# 01-MCU-V2_2.net
KiCad netlist of a schematic drawn in Altium Designer
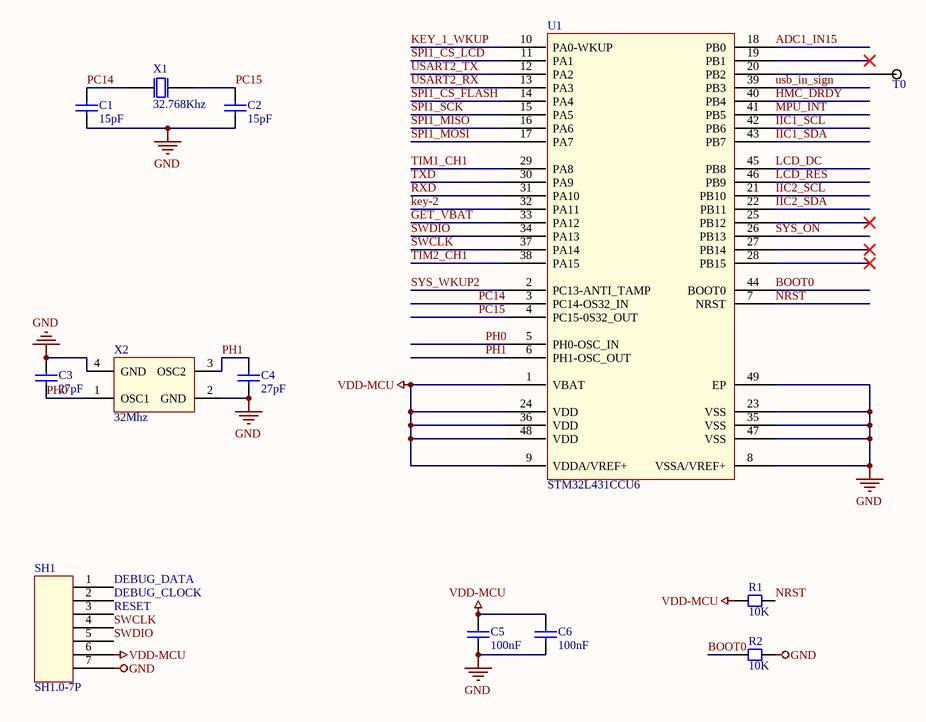
[diagram p0: 01-MCU-V2.2.SchDoc]

(export (version "E")
  (design (tool "Eeschema 10.0.6"))
  (components
    (comp (ref "C1")
      (value "15pF")
      (footprint "CC1005-0402")
      (description "贴片电容")
      (libsource (lib "tianxiaohua_Schlib") (part "Chip capacitor"))
    )
    (comp (ref "C2")
      (value "15pF")
      (footprint "CC1005-0402")
      (description "贴片电容")
      (libsource (lib "tianxiaohua_Schlib") (part "Chip capacitor"))
    )
    (comp (ref "C3")
      (value "27pF")
      (footprint "CC1005-0402")
      (description "贴片电容")
      (libsource (lib "tianxiaohua_Schlib") (part "Chip capacitor"))
    )
    (comp (ref "C4")
      (value "27pF")
      (footprint "CC1005-0402")
      (description "贴片电容")
      (libsource (lib "tianxiaohua_Schlib") (part "Chip capacitor"))
    )
    (comp (ref "C5")
      (value "100nF")
      (footprint "CC1005-0402")
      (description "贴片电容")
      (libsource (lib "tianxiaohua_Schlib") (part "Chip capacitor"))
    )
    (comp (ref "C6")
      (value "100nF")
      (footprint "CC1005-0402")
      (description "贴片电容")
      (libsource (lib "tianxiaohua_Schlib") (part "Chip capacitor"))
    )
    (comp (ref "R1")
      (value "10K")
      (footprint "CR1005-0402")
      (description "贴片电阻")
      (libsource (lib "tianxiaohua_Schlib") (part "Chip resistor"))
    )
    (comp (ref "R2")
      (value "10K")
      (footprint "CR1005-0402")
      (description "贴片电阻")
      (libsource (lib "tianxiaohua_Schlib") (part "Chip resistor"))
    )
    (comp (ref "SH1")
      (value "SH1.0-7P")
      (footprint "SH1.0-7P")
      (description "间距为1mm的端子")
      (libsource (lib "tianxiaohua_Schlib") (part "SH1.0-7P"))
    )
    (comp (ref "T0") (value "测试点") (footprint "测试点") (libsource (lib "tianxiaohua_Schlib") (part "测试点")))
    (comp (ref "U1")
      (value "STM32L431CCU6")
      (footprint "STM32-UFQFPN48_N")
      (description "stm32低功耗单片机 主频80MHz")
      (libsource (lib "tianxiaohua_Schlib") (part "STM32L431CCU6"))
    )
    (comp (ref "X1")
      (value "32.768Khz")
      (footprint "XTAL-2012")
      (description "2012封装的时钟晶振")
      (libsource (lib "tianxiaohua_Schlib") (part "XTAL 2012"))
    )
    (comp (ref "X2")
      (value "32Mhz")
      (footprint "XTAL-2016")
      (description "2016封装的晶振")
      (libsource (lib "tianxiaohua_Schlib") (part "XTAL 2016"))
    )
  )
  (nets
    (net (code "1") (name "/ADC1_IN15") (class "Default")
      (node (ref "U1") (pin "18") (pinfunction "PB0_18") (pintype "passive"))
    )
    (net (code "2") (name "/BOOT0") (class "Default")
      (node (ref "R2") (pin "2") (pinfunction "2_2") (pintype "passive"))
      (node (ref "U1") (pin "44") (pinfunction "BOOT0_44") (pintype "passive"))
    )
    (net (code "3") (name "/DEBUG_CLOCK") (class "Default")
      (node (ref "SH1") (pin "2") (pinfunction "2_2") (pintype "passive"))
    )
    (net (code "4") (name "/DEBUG_DATA") (class "Default") (node (ref "SH1") (pin "1") (pintype "passive")))
    (net (code "5") (name "/GET_VBAT") (class "Default")
      (node (ref "U1") (pin "33") (pinfunction "PA12_33") (pintype "passive"))
    )
    (net (code "6") (name "/HMC_DRDY") (class "Default")
      (node (ref "U1") (pin "40") (pinfunction "PB4_40") (pintype "passive"))
    )
    (net (code "7") (name "/IIC1_SCL") (class "Default")
      (node (ref "U1") (pin "42") (pinfunction "PB6_42") (pintype "passive"))
    )
    (net (code "8") (name "/IIC1_SDA") (class "Default")
      (node (ref "U1") (pin "43") (pinfunction "PB7_43") (pintype "passive"))
    )
    (net (code "9") (name "/IIC2_SCL") (class "Default")
      (node (ref "U1") (pin "21") (pinfunction "PB10_21") (pintype "passive"))
    )
    (net (code "10") (name "/IIC2_SDA") (class "Default")
      (node (ref "U1") (pin "22") (pinfunction "PB11_22") (pintype "passive"))
    )
    (net (code "11") (name "/KEY_1_WKUP") (class "Default")
      (node (ref "U1") (pin "10") (pinfunction "PA0-WKUP_10") (pintype "passive"))
    )
    (net (code "12") (name "/LCD_DC") (class "Default")
      (node (ref "U1") (pin "45") (pinfunction "PB8_45") (pintype "passive"))
    )
    (net (code "13") (name "/LCD_RES") (class "Default")
      (node (ref "U1") (pin "46") (pinfunction "PB9_46") (pintype "passive"))
    )
    (net (code "14") (name "/MPU_INT") (class "Default")
      (node (ref "U1") (pin "41") (pinfunction "PB5_41") (pintype "passive"))
    )
    (net (code "15") (name "/NRST") (class "Default")
      (node (ref "R1") (pin "1") (pinfunction "1_1") (pintype "passive"))
      (node (ref "U1") (pin "7") (pinfunction "NRST_7") (pintype "passive"))
    )
    (net (code "16") (name "/PC14") (class "Default")
      (node (ref "C1") (pin "2") (pinfunction "2_2") (pintype "passive"))
      (node (ref "U1") (pin "3") (pinfunction "PC14-OS32_IN_3") (pintype "passive"))
      (node (ref "X1") (pin "2") (pinfunction "2_2") (pintype "passive"))
    )
    (net (code "17") (name "/PC15") (class "Default")
      (node (ref "C2") (pin "2") (pinfunction "2_2") (pintype "passive"))
      (node (ref "U1") (pin "4") (pinfunction "PC15-0S32_OUT_4") (pintype "passive"))
      (node (ref "X1") (pin "1") (pinfunction "1_1") (pintype "passive"))
    )
    (net (code "18") (name "/PH0") (class "Default")
      (node (ref "C3") (pin "1") (pinfunction "1_1") (pintype "passive"))
      (node (ref "U1") (pin "5") (pinfunction "PH0-OSC_IN_5") (pintype "passive"))
      (node (ref "X2") (pin "1") (pinfunction "OSC1_1") (pintype "passive"))
    )
    (net (code "19") (name "/PH1") (class "Default")
      (node (ref "C4") (pin "2") (pinfunction "2_2") (pintype "passive"))
      (node (ref "U1") (pin "6") (pinfunction "PH1-OSC_OUT_6") (pintype "passive"))
      (node (ref "X2") (pin "3") (pinfunction "OSC2_3") (pintype "passive"))
    )
    (net (code "20") (name "/RESET") (class "Default") (node (ref "SH1") (pin "3") (pintype "passive")))
    (net (code "21") (name "/RXD") (class "Default")
      (node (ref "U1") (pin "31") (pinfunction "PA10_31") (pintype "passive"))
    )
    (net (code "22") (name "/SPI1_CS_FLASH") (class "Default")
      (node (ref "U1") (pin "14") (pinfunction "PA4_14") (pintype "passive"))
    )
    (net (code "23") (name "/SPI1_CS_LCD") (class "Default")
      (node (ref "U1") (pin "11") (pinfunction "PA1_11") (pintype "passive"))
    )
    (net (code "24") (name "/SPI1_MISO") (class "Default")
      (node (ref "U1") (pin "16") (pinfunction "PA6_16") (pintype "passive"))
    )
    (net (code "25") (name "/SPI1_MOSI") (class "Default")
      (node (ref "U1") (pin "17") (pinfunction "PA7_17") (pintype "passive"))
    )
    (net (code "26") (name "/SPI1_SCK") (class "Default")
      (node (ref "U1") (pin "15") (pinfunction "PA5_15") (pintype "passive"))
    )
    (net (code "27") (name "/SWCLK") (class "Default")
      (node (ref "SH1") (pin "4") (pinfunction "4_4") (pintype "passive"))
      (node (ref "U1") (pin "37") (pinfunction "PA14_37") (pintype "passive"))
    )
    (net (code "28") (name "/SWDIO") (class "Default")
      (node (ref "SH1") (pin "5") (pintype "passive"))
      (node (ref "U1") (pin "34") (pinfunction "PA13_34") (pintype "passive"))
    )
    (net (code "29") (name "/SYS_ON") (class "Default")
      (node (ref "U1") (pin "26") (pinfunction "PB13_26") (pintype "passive"))
    )
    (net (code "30") (name "/SYS_WKUP2") (class "Default")
      (node (ref "U1") (pin "2") (pinfunction "PC13-ANTI_TAMP_2") (pintype "passive"))
    )
    (net (code "31") (name "/TIM1_CH1") (class "Default")
      (node (ref "U1") (pin "29") (pinfunction "PA8_29") (pintype "passive"))
    )
    (net (code "32") (name "/TIM2_CH1") (class "Default")
      (node (ref "U1") (pin "38") (pinfunction "PA15_38") (pintype "passive"))
    )
    (net (code "33") (name "/TXD") (class "Default")
      (node (ref "U1") (pin "30") (pinfunction "PA9_30") (pintype "passive"))
    )
    (net (code "34") (name "/USART2_RX") (class "Default")
      (node (ref "U1") (pin "13") (pinfunction "PA3_13") (pintype "passive"))
    )
    (net (code "35") (name "/USART2_TX") (class "Default")
      (node (ref "U1") (pin "12") (pinfunction "PA2_12") (pintype "passive"))
    )
    (net (code "36") (name "/key-2") (class "Default")
      (node (ref "U1") (pin "32") (pinfunction "PA11_32") (pintype "passive"))
    )
    (net (code "37") (name "/usb_in_sign") (class "Default")
      (node (ref "U1") (pin "39") (pinfunction "PB3_39") (pintype "passive"))
    )
    (net (code "38") (name "GND") (class "Default")
      (node (ref "C1") (pin "1") (pinfunction "1_1") (pintype "passive"))
      (node (ref "C2") (pin "1") (pinfunction "1_1") (pintype "passive"))
      (node (ref "C3") (pin "2") (pinfunction "2_2") (pintype "passive"))
      (node (ref "C4") (pin "1") (pinfunction "1_1") (pintype "passive"))
      (node (ref "C5") (pin "1") (pinfunction "1_1") (pintype "passive"))
      (node (ref "C6") (pin "1") (pinfunction "1_1") (pintype "passive"))
      (node (ref "R2") (pin "1") (pinfunction "1_1") (pintype "passive"))
      (node (ref "SH1") (pin "7") (pinfunction "7_7") (pintype "passive"))
      (node (ref "U1") (pin "23") (pinfunction "VSS_23") (pintype "passive"))
      (node (ref "U1") (pin "35") (pinfunction "VSS_35") (pintype "passive"))
      (node (ref "U1") (pin "47") (pinfunction "VSS_47") (pintype "passive"))
      (node (ref "U1") (pin "49") (pinfunction "EP_49") (pintype "passive"))
      (node (ref "U1") (pin "8") (pinfunction "VSSA/VREF+_8") (pintype "passive"))
      (node (ref "X2") (pin "2") (pinfunction "GND_2") (pintype "passive"))
      (node (ref "X2") (pin "4") (pinfunction "GND_4") (pintype "passive"))
    )
    (net (code "39") (name "Net-(U1-PB2)") (class "Default")
      (node (ref "T0") (pin "1") (pinfunction "1_1") (pintype "passive"))
      (node (ref "U1") (pin "20") (pinfunction "PB2_20") (pintype "passive"))
    )
    (net (code "40") (name "VDD-MCU") (class "Default")
      (node (ref "C5") (pin "2") (pinfunction "2_2") (pintype "passive"))
      (node (ref "C6") (pin "2") (pinfunction "2_2") (pintype "passive"))
      (node (ref "R1") (pin "2") (pinfunction "2_2") (pintype "passive"))
      (node (ref "SH1") (pin "6") (pinfunction "6_6") (pintype "passive"))
      (node (ref "U1") (pin "1") (pinfunction "VBAT_1") (pintype "passive"))
      (node (ref "U1") (pin "24") (pinfunction "VDD_24") (pintype "passive"))
      (node (ref "U1") (pin "36") (pinfunction "VDD_36") (pintype "passive"))
      (node (ref "U1") (pin "48") (pinfunction "VDD_48") (pintype "passive"))
      (node (ref "U1") (pin "9") (pinfunction "VDDA/VREF+_9") (pintype "passive"))
    )
    (net (code "41") (name "unconnected-(U1-PB1-Pad19)") (class "Default")
      (node (ref "U1") (pin "19") (pinfunction "PB1_19") (pintype "passive+no_connect"))
    )
    (net (code "42") (name "unconnected-(U1-PB12-Pad25)") (class "Default")
      (node (ref "U1") (pin "25") (pinfunction "PB12_25") (pintype "passive+no_connect"))
    )
    (net (code "43") (name "unconnected-(U1-PB14-Pad27)") (class "Default")
      (node (ref "U1") (pin "27") (pinfunction "PB14_27") (pintype "passive+no_connect"))
    )
    (net (code "44") (name "unconnected-(U1-PB15-Pad28)") (class "Default")
      (node (ref "U1") (pin "28") (pinfunction "PB15_28") (pintype "passive+no_connect"))
    )
  )
)
